# M191X.net
KiCad netlist of a schematic drawn in EAGLE
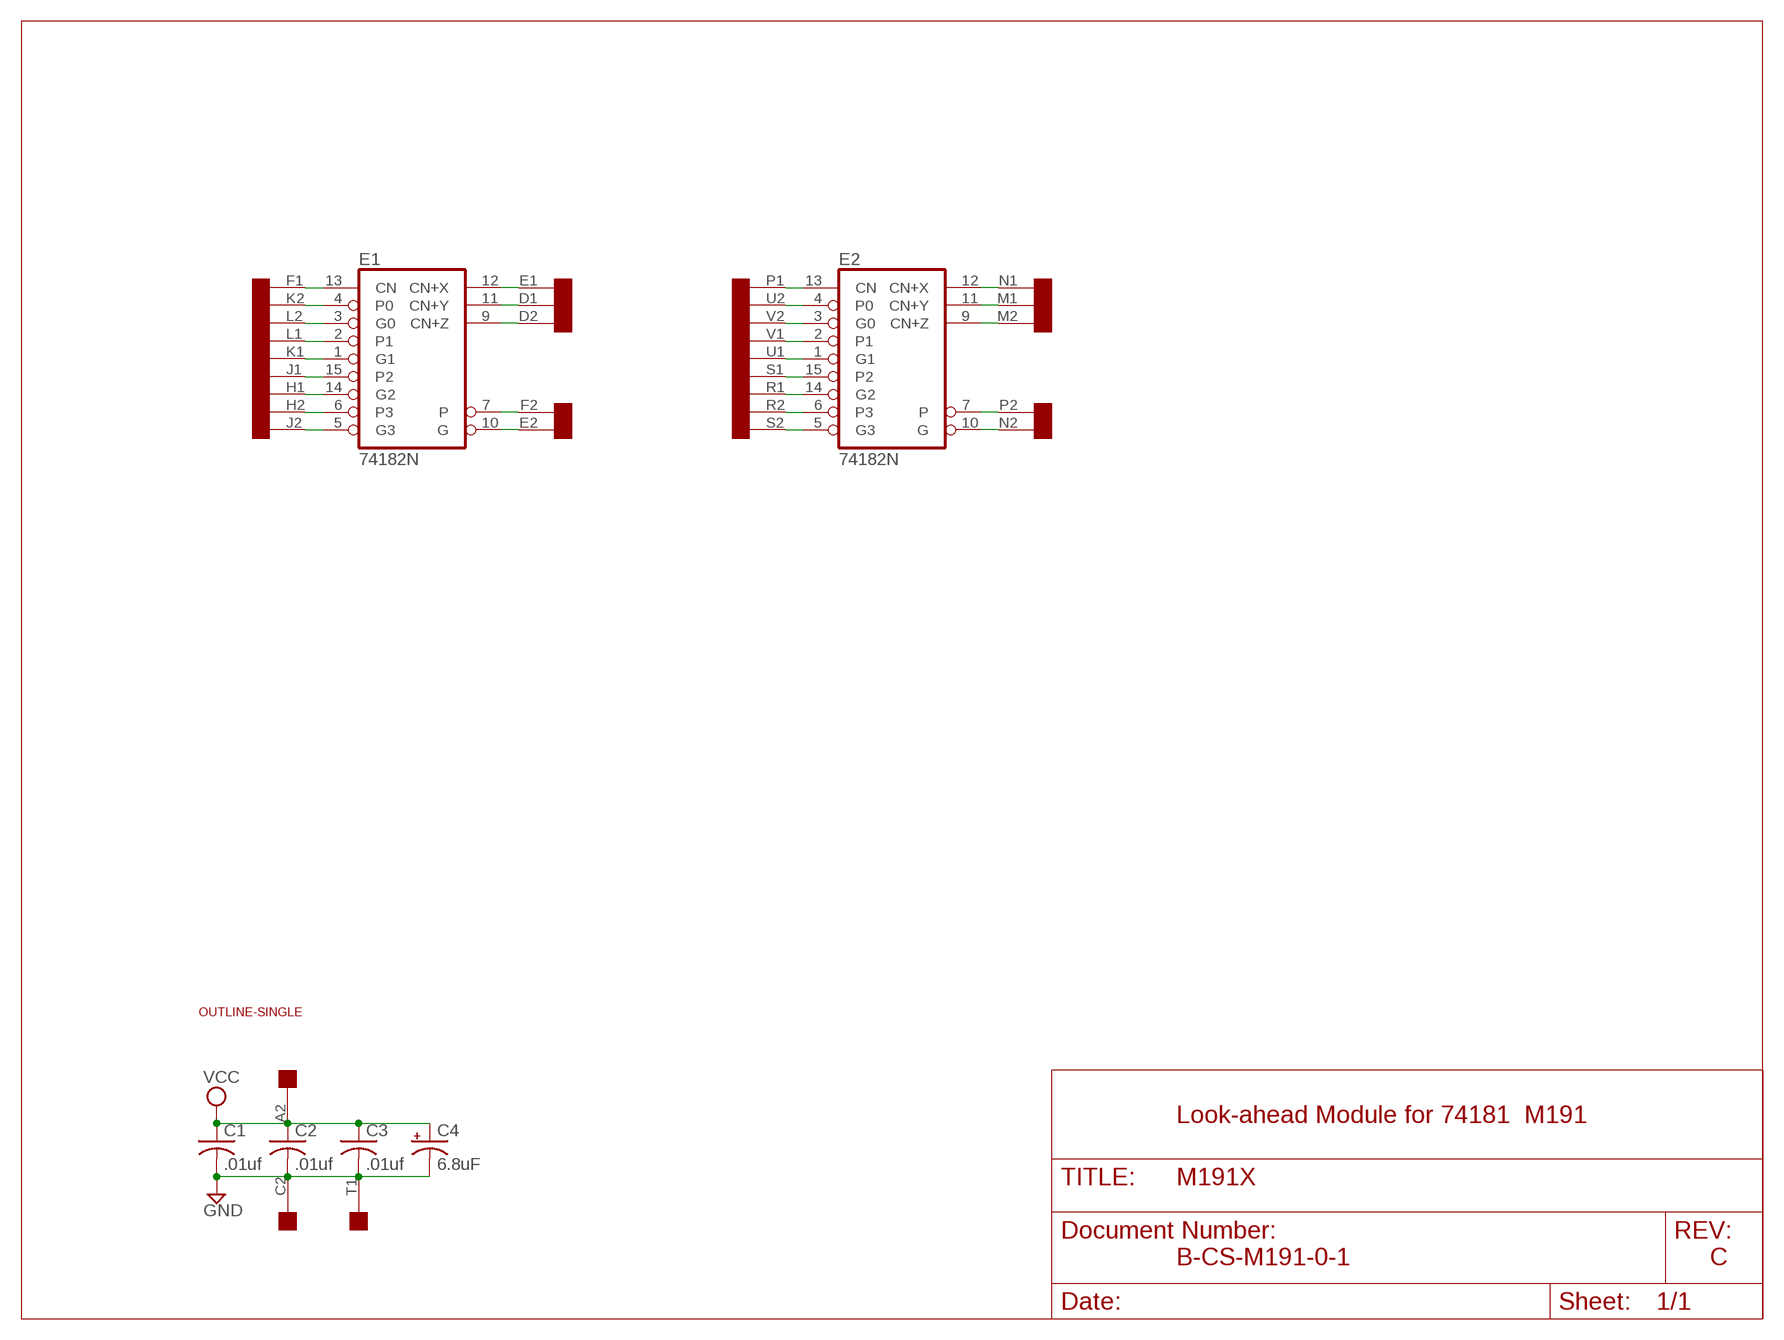
[diagram p0: schematic, sheet 1]

(export (version "E")
  (design (tool "Eeschema 10.0.6"))
  (components
    (comp (ref "C1")
      (value ".01uf")
      (footprint "eagle-import:C050-025X075")
      (libsource (lib "eagle-import") (part "C-US050-025X075"))
    )
    (comp (ref "C2")
      (value ".01uf")
      (footprint "eagle-import:C050-025X075")
      (libsource (lib "eagle-import") (part "C-US050-025X075"))
    )
    (comp (ref "C3")
      (value ".01uf")
      (footprint "eagle-import:C050-025X075")
      (libsource (lib "eagle-import") (part "C-US050-025X075"))
    )
    (comp (ref "C4")
      (value "6.8uF")
      (footprint "eagle-import:E22-6")
      (libsource (lib "eagle-import") (part "CPOL-USE22-6AXIAL"))
    )
    (comp (ref "E1")
      (value "74182N")
      (footprint "eagle-import:DIL16")
      (libsource (lib "eagle-import") (part "74182NS"))
    )
    (comp (ref "E2")
      (value "74182N")
      (footprint "eagle-import:DIL16")
      (libsource (lib "eagle-import") (part "74182NS"))
    )
    (comp (ref "U$1")
      (value "OUTLINE-SINGLE")
      (footprint "eagle-import:SINGLE")
      (libsource (lib "eagle-import") (part "OUTLINE-SINGLE"))
    )
    (comp (ref "U$2")
      (value "EDGE-2CONNECTOR")
      (footprint "eagle-import:EDGE-CON2")
      (libsource (lib "eagle-import") (part "EDGE-2CONNECTOR"))
    )
  )
  (nets
    (net (code "1") (name "GND") (class "Default")
      (node (ref "C1") (pin "2") (pinfunction "2_2") (pintype "passive"))
      (node (ref "C2") (pin "2") (pinfunction "2_2") (pintype "passive"))
      (node (ref "C3") (pin "2") (pinfunction "2_2") (pintype "passive"))
      (node (ref "C4") (pin "-") (pinfunction "-_-") (pintype "passive"))
      (node (ref "U$2") (pin "C2") (pinfunction "1_C2") (pintype "bidirectional"))
      (node (ref "U$2") (pin "T1") (pinfunction "1_T1") (pintype "bidirectional"))
    )
    (net (code "2") (name "Net-(E1A-CN)") (class "Default")
      (node (ref "E1") (pin "13") (pinfunction "CN_13") (pintype "input"))
      (node (ref "U$2") (pin "F1") (pinfunction "1_F1") (pintype "bidirectional"))
    )
    (net (code "3") (name "Net-(E1A-CN+X)") (class "Default")
      (node (ref "E1") (pin "12") (pinfunction "CN+X_12") (pintype "output"))
      (node (ref "U$2") (pin "E1") (pinfunction "1_E1") (pintype "bidirectional"))
    )
    (net (code "4") (name "Net-(E1A-CN+Y)") (class "Default")
      (node (ref "E1") (pin "11") (pinfunction "CN+Y_11") (pintype "output"))
      (node (ref "U$2") (pin "D1") (pinfunction "1_D1") (pintype "bidirectional"))
    )
    (net (code "5") (name "Net-(E1A-CN+Z)") (class "Default")
      (node (ref "E1") (pin "9") (pinfunction "CN+Z_9") (pintype "output"))
      (node (ref "U$2") (pin "D2") (pinfunction "1_D2") (pintype "bidirectional"))
    )
    (net (code "6") (name "Net-(E1A-G)") (class "Default")
      (node (ref "E1") (pin "10") (pinfunction "G_10") (pintype "output"))
      (node (ref "U$2") (pin "E2") (pinfunction "1_E2") (pintype "bidirectional"))
    )
    (net (code "7") (name "Net-(E1A-G0)") (class "Default")
      (node (ref "E1") (pin "3") (pinfunction "G0_3") (pintype "input"))
      (node (ref "U$2") (pin "L2") (pinfunction "1_L2") (pintype "bidirectional"))
    )
    (net (code "8") (name "Net-(E1A-G1)") (class "Default")
      (node (ref "E1") (pin "1") (pinfunction "G1_1") (pintype "input"))
      (node (ref "U$2") (pin "K1") (pinfunction "1_K1") (pintype "bidirectional"))
    )
    (net (code "9") (name "Net-(E1A-G2)") (class "Default")
      (node (ref "E1") (pin "14") (pinfunction "G2_14") (pintype "input"))
      (node (ref "U$2") (pin "H1") (pinfunction "1_H1") (pintype "bidirectional"))
    )
    (net (code "10") (name "Net-(E1A-G3)") (class "Default")
      (node (ref "E1") (pin "5") (pinfunction "G3_5") (pintype "input"))
      (node (ref "U$2") (pin "J2") (pinfunction "1_J2") (pintype "bidirectional"))
    )
    (net (code "11") (name "Net-(E1A-P)") (class "Default")
      (node (ref "E1") (pin "7") (pinfunction "P_7") (pintype "output"))
      (node (ref "U$2") (pin "F2") (pinfunction "1_F2") (pintype "bidirectional"))
    )
    (net (code "12") (name "Net-(E1A-P0)") (class "Default")
      (node (ref "E1") (pin "4") (pinfunction "P0_4") (pintype "input"))
      (node (ref "U$2") (pin "K2") (pinfunction "1_K2") (pintype "bidirectional"))
    )
    (net (code "13") (name "Net-(E1A-P1)") (class "Default")
      (node (ref "E1") (pin "2") (pinfunction "P1_2") (pintype "input"))
      (node (ref "U$2") (pin "L1") (pinfunction "1_L1") (pintype "bidirectional"))
    )
    (net (code "14") (name "Net-(E1A-P2)") (class "Default")
      (node (ref "E1") (pin "15") (pinfunction "P2_15") (pintype "input"))
      (node (ref "U$2") (pin "J1") (pinfunction "1_J1") (pintype "bidirectional"))
    )
    (net (code "15") (name "Net-(E1A-P3)") (class "Default")
      (node (ref "E1") (pin "6") (pinfunction "P3_6") (pintype "input"))
      (node (ref "U$2") (pin "H2") (pinfunction "1_H2") (pintype "bidirectional"))
    )
    (net (code "16") (name "Net-(E2A-CN)") (class "Default")
      (node (ref "E2") (pin "13") (pinfunction "CN_13") (pintype "input"))
      (node (ref "U$2") (pin "P1") (pinfunction "1_P1") (pintype "bidirectional"))
    )
    (net (code "17") (name "Net-(E2A-CN+X)") (class "Default")
      (node (ref "E2") (pin "12") (pinfunction "CN+X_12") (pintype "output"))
      (node (ref "U$2") (pin "N1") (pinfunction "1_N1") (pintype "bidirectional"))
    )
    (net (code "18") (name "Net-(E2A-CN+Y)") (class "Default")
      (node (ref "E2") (pin "11") (pinfunction "CN+Y_11") (pintype "output"))
      (node (ref "U$2") (pin "M1") (pinfunction "1_M1") (pintype "bidirectional"))
    )
    (net (code "19") (name "Net-(E2A-CN+Z)") (class "Default")
      (node (ref "E2") (pin "9") (pinfunction "CN+Z_9") (pintype "output"))
      (node (ref "U$2") (pin "M2") (pinfunction "1_M2") (pintype "bidirectional"))
    )
    (net (code "20") (name "Net-(E2A-G)") (class "Default")
      (node (ref "E2") (pin "10") (pinfunction "G_10") (pintype "output"))
      (node (ref "U$2") (pin "N2") (pinfunction "1_N2") (pintype "bidirectional"))
    )
    (net (code "21") (name "Net-(E2A-G0)") (class "Default")
      (node (ref "E2") (pin "3") (pinfunction "G0_3") (pintype "input"))
      (node (ref "U$2") (pin "V2") (pinfunction "1_V2") (pintype "bidirectional"))
    )
    (net (code "22") (name "Net-(E2A-G1)") (class "Default")
      (node (ref "E2") (pin "1") (pinfunction "G1_1") (pintype "input"))
      (node (ref "U$2") (pin "U1") (pinfunction "1_U1") (pintype "bidirectional"))
    )
    (net (code "23") (name "Net-(E2A-G2)") (class "Default")
      (node (ref "E2") (pin "14") (pinfunction "G2_14") (pintype "input"))
      (node (ref "U$2") (pin "R1") (pinfunction "1_R1") (pintype "bidirectional"))
    )
    (net (code "24") (name "Net-(E2A-G3)") (class "Default")
      (node (ref "E2") (pin "5") (pinfunction "G3_5") (pintype "input"))
      (node (ref "U$2") (pin "S2") (pinfunction "1_S2") (pintype "bidirectional"))
    )
    (net (code "25") (name "Net-(E2A-P)") (class "Default")
      (node (ref "E2") (pin "7") (pinfunction "P_7") (pintype "output"))
      (node (ref "U$2") (pin "P2") (pinfunction "1_P2") (pintype "bidirectional"))
    )
    (net (code "26") (name "Net-(E2A-P0)") (class "Default")
      (node (ref "E2") (pin "4") (pinfunction "P0_4") (pintype "input"))
      (node (ref "U$2") (pin "U2") (pinfunction "1_U2") (pintype "bidirectional"))
    )
    (net (code "27") (name "Net-(E2A-P1)") (class "Default")
      (node (ref "E2") (pin "2") (pinfunction "P1_2") (pintype "input"))
      (node (ref "U$2") (pin "V1") (pinfunction "1_V1") (pintype "bidirectional"))
    )
    (net (code "28") (name "Net-(E2A-P2)") (class "Default")
      (node (ref "E2") (pin "15") (pinfunction "P2_15") (pintype "input"))
      (node (ref "U$2") (pin "S1") (pinfunction "1_S1") (pintype "bidirectional"))
    )
    (net (code "29") (name "Net-(E2A-P3)") (class "Default")
      (node (ref "E2") (pin "6") (pinfunction "P3_6") (pintype "input"))
      (node (ref "U$2") (pin "R2") (pinfunction "1_R2") (pintype "bidirectional"))
    )
    (net (code "30") (name "VCC") (class "Default")
      (node (ref "C1") (pin "1") (pinfunction "1_1") (pintype "passive"))
      (node (ref "C2") (pin "1") (pinfunction "1_1") (pintype "passive"))
      (node (ref "C3") (pin "1") (pinfunction "1_1") (pintype "passive"))
      (node (ref "C4") (pin "+") (pinfunction "+_+") (pintype "passive"))
      (node (ref "U$2") (pin "A2") (pinfunction "1_A2") (pintype "bidirectional"))
    )
  )
)
